# doorbell.net
KiCad netlist of a schematic drawn in EAGLE
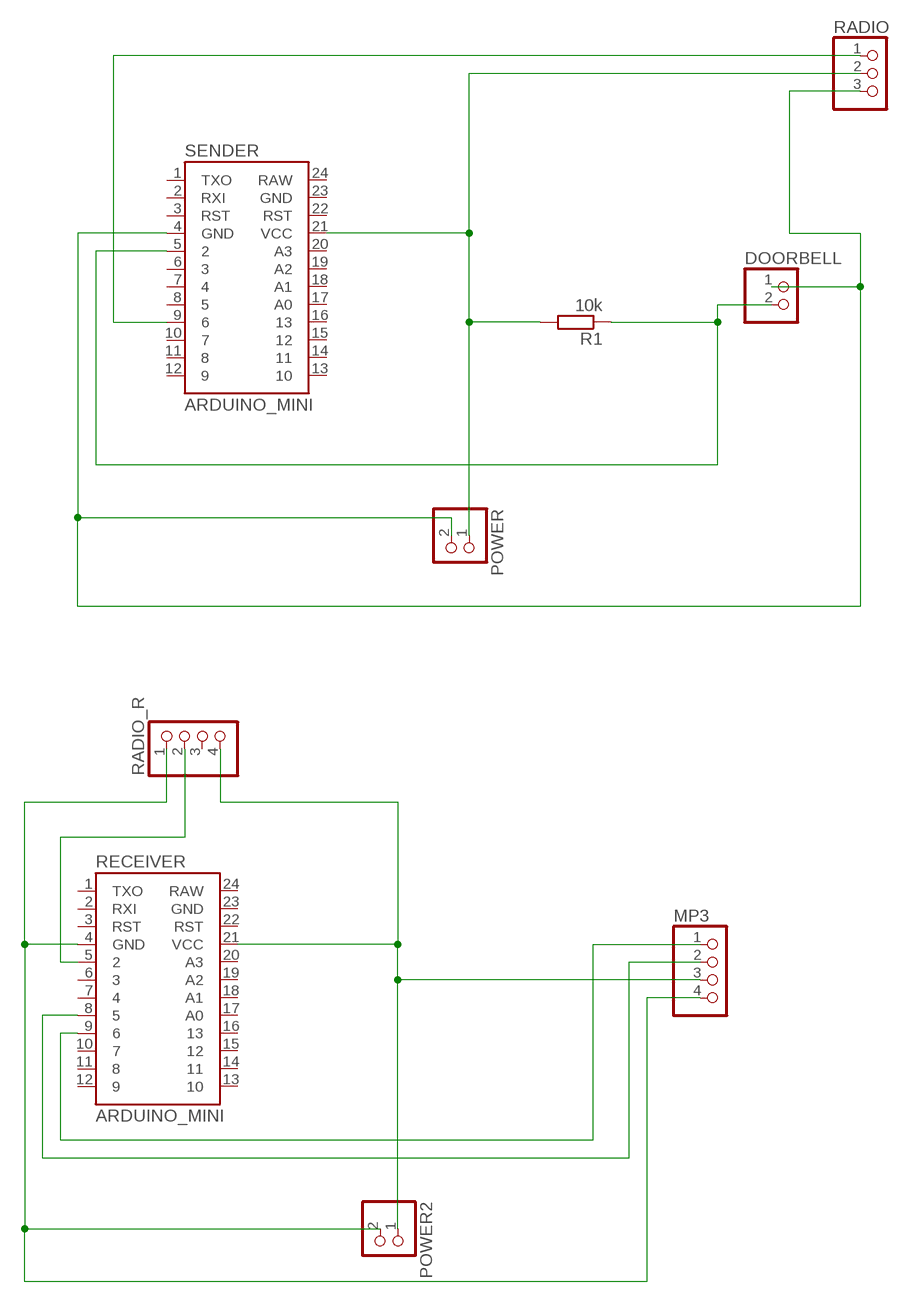
[diagram p0: schematic, sheet 1]

(export (version "E")
  (design (tool "Eeschema 10.0.6"))
  (components
    (comp (ref "DOORBELL")
      (value "PINHD-1X2/90")
      (footprint "eagle-import:1X02_90")
      (libsource (lib "eagle-import") (part "PINHD-1X2/90"))
    )
    (comp (ref "MP3")
      (value "PINHD-1X4/90")
      (footprint "eagle-import:1X04_90")
      (libsource (lib "eagle-import") (part "PINHD-1X4/90"))
    )
    (comp (ref "POWER")
      (value "PINHD-1X2/90")
      (footprint "eagle-import:1X02_90")
      (libsource (lib "eagle-import") (part "PINHD-1X2/90"))
    )
    (comp (ref "POWER2")
      (value "PINHD-1X2/90")
      (footprint "eagle-import:1X02_90")
      (libsource (lib "eagle-import") (part "PINHD-1X2/90"))
    )
    (comp (ref "R1")
      (value "10k")
      (footprint "eagle-import:0207_10")
      (libsource (lib "eagle-import") (part "R0207/10"))
    )
    (comp (ref "RADIO")
      (value "PINHD-1X3/90")
      (footprint "eagle-import:1X03_90")
      (libsource (lib "eagle-import") (part "PINHD-1X3/90"))
    )
    (comp (ref "RADIO_R")
      (value "PINHD-1X4/90")
      (footprint "eagle-import:1X04_90")
      (libsource (lib "eagle-import") (part "PINHD-1X4/90"))
    )
    (comp (ref "RECEIVER")
      (value "ARDUINO_MINI")
      (footprint "eagle-import:ARDUINO_MINI")
      (libsource (lib "eagle-import") (part "ARDUINO_MINI"))
    )
    (comp (ref "SENDER")
      (value "ARDUINO_MINI")
      (footprint "eagle-import:ARDUINO_MINI")
      (libsource (lib "eagle-import") (part "ARDUINO_MINI"))
    )
  )
  (nets
    (net (code "1") (name "Net-(DOORBELL-Pad1)") (class "Default")
      (node (ref "DOORBELL") (pin "1") (pinfunction "1_1") (pintype "passive"))
      (node (ref "POWER") (pin "2") (pinfunction "2_2") (pintype "passive"))
      (node (ref "RADIO") (pin "3") (pinfunction "3_3") (pintype "passive"))
      (node (ref "SENDER") (pin "4") (pinfunction "GND_4") (pintype "bidirectional"))
    )
    (net (code "2") (name "Net-(MP3-Pad4)") (class "Default")
      (node (ref "MP3") (pin "4") (pinfunction "4_4") (pintype "passive"))
      (node (ref "POWER2") (pin "2") (pinfunction "2_2") (pintype "passive"))
      (node (ref "RADIO_R") (pin "1") (pinfunction "1_1") (pintype "passive"))
      (node (ref "RECEIVER") (pin "4") (pinfunction "GND_4") (pintype "bidirectional"))
    )
    (net (code "3") (name "Net-(RECEIVER-2)") (class "Default")
      (node (ref "RADIO_R") (pin "2") (pinfunction "2_2") (pintype "passive"))
      (node (ref "RECEIVER") (pin "5") (pinfunction "2_5") (pintype "bidirectional"))
    )
    (net (code "4") (name "Net-(RECEIVER-5)") (class "Default")
      (node (ref "MP3") (pin "2") (pinfunction "2_2") (pintype "passive"))
      (node (ref "RECEIVER") (pin "8") (pinfunction "5_8") (pintype "bidirectional"))
    )
    (net (code "5") (name "Net-(RECEIVER-6)") (class "Default")
      (node (ref "MP3") (pin "1") (pinfunction "1_1") (pintype "passive"))
      (node (ref "RECEIVER") (pin "9") (pinfunction "6_9") (pintype "bidirectional"))
    )
    (net (code "6") (name "Net-(RECEIVER-VCC)") (class "Default")
      (node (ref "MP3") (pin "3") (pinfunction "3_3") (pintype "passive"))
      (node (ref "POWER2") (pin "1") (pinfunction "1_1") (pintype "passive"))
      (node (ref "RADIO_R") (pin "4") (pinfunction "4_4") (pintype "passive"))
      (node (ref "RECEIVER") (pin "21") (pinfunction "VCC_21") (pintype "bidirectional"))
    )
    (net (code "7") (name "Net-(SENDER-2)") (class "Default")
      (node (ref "DOORBELL") (pin "2") (pinfunction "2_2") (pintype "passive"))
      (node (ref "R1") (pin "1") (pinfunction "1_1") (pintype "passive"))
      (node (ref "SENDER") (pin "5") (pinfunction "2_5") (pintype "bidirectional"))
    )
    (net (code "8") (name "Net-(SENDER-6)") (class "Default")
      (node (ref "RADIO") (pin "1") (pinfunction "1_1") (pintype "passive"))
      (node (ref "SENDER") (pin "9") (pinfunction "6_9") (pintype "bidirectional"))
    )
    (net (code "9") (name "Net-(SENDER-VCC)") (class "Default")
      (node (ref "POWER") (pin "1") (pinfunction "1_1") (pintype "passive"))
      (node (ref "R1") (pin "2") (pinfunction "2_2") (pintype "passive"))
      (node (ref "RADIO") (pin "2") (pinfunction "2_2") (pintype "passive"))
      (node (ref "SENDER") (pin "21") (pinfunction "VCC_21") (pintype "bidirectional"))
    )
    (net (code "10") (name "unconnected-(RADIO_R-Pad3)") (class "Default")
      (node (ref "RADIO_R") (pin "3") (pinfunction "3_3") (pintype "passive"))
    )
    (net (code "11") (name "unconnected-(RECEIVER-3-Pad6)") (class "Default")
      (node (ref "RECEIVER") (pin "6") (pinfunction "3_6") (pintype "bidirectional"))
    )
    (net (code "12") (name "unconnected-(RECEIVER-4-Pad7)") (class "Default")
      (node (ref "RECEIVER") (pin "7") (pinfunction "4_7") (pintype "bidirectional"))
    )
    (net (code "13") (name "unconnected-(RECEIVER-7-Pad10)") (class "Default")
      (node (ref "RECEIVER") (pin "10") (pinfunction "7_10") (pintype "bidirectional"))
    )
    (net (code "14") (name "unconnected-(RECEIVER-8-Pad11)") (class "Default")
      (node (ref "RECEIVER") (pin "11") (pinfunction "8_11") (pintype "bidirectional"))
    )
    (net (code "15") (name "unconnected-(RECEIVER-9-Pad12)") (class "Default")
      (node (ref "RECEIVER") (pin "12") (pinfunction "9_12") (pintype "bidirectional"))
    )
    (net (code "16") (name "unconnected-(RECEIVER-10-Pad13)") (class "Default")
      (node (ref "RECEIVER") (pin "13") (pinfunction "10_13") (pintype "bidirectional"))
    )
    (net (code "17") (name "unconnected-(RECEIVER-11-Pad14)") (class "Default")
      (node (ref "RECEIVER") (pin "14") (pinfunction "11_14") (pintype "bidirectional"))
    )
    (net (code "18") (name "unconnected-(RECEIVER-12-Pad15)") (class "Default")
      (node (ref "RECEIVER") (pin "15") (pinfunction "12_15") (pintype "bidirectional"))
    )
    (net (code "19") (name "unconnected-(RECEIVER-13-Pad16)") (class "Default")
      (node (ref "RECEIVER") (pin "16") (pinfunction "13_16") (pintype "bidirectional"))
    )
    (net (code "20") (name "unconnected-(RECEIVER-A0-Pad17)") (class "Default")
      (node (ref "RECEIVER") (pin "17") (pinfunction "A0_17") (pintype "bidirectional"))
    )
    (net (code "21") (name "unconnected-(RECEIVER-A1-Pad18)") (class "Default")
      (node (ref "RECEIVER") (pin "18") (pinfunction "A1_18") (pintype "bidirectional"))
    )
    (net (code "22") (name "unconnected-(RECEIVER-A2-Pad19)") (class "Default")
      (node (ref "RECEIVER") (pin "19") (pinfunction "A2_19") (pintype "bidirectional"))
    )
    (net (code "23") (name "unconnected-(RECEIVER-A3-Pad20)") (class "Default")
      (node (ref "RECEIVER") (pin "20") (pinfunction "A3_20") (pintype "bidirectional"))
    )
    (net (code "24") (name "unconnected-(RECEIVER-GND-Pad23)") (class "Default")
      (node (ref "RECEIVER") (pin "23") (pinfunction "GND_23") (pintype "bidirectional"))
    )
    (net (code "25") (name "unconnected-(RECEIVER-RAW-Pad24)") (class "Default")
      (node (ref "RECEIVER") (pin "24") (pinfunction "RAW_24") (pintype "bidirectional"))
    )
    (net (code "26") (name "unconnected-(RECEIVER-RST-Pad3)") (class "Default")
      (node (ref "RECEIVER") (pin "3") (pinfunction "RST_3") (pintype "bidirectional"))
    )
    (net (code "27") (name "unconnected-(RECEIVER-RST-Pad22)") (class "Default")
      (node (ref "RECEIVER") (pin "22") (pinfunction "RST_22") (pintype "bidirectional"))
    )
    (net (code "28") (name "unconnected-(RECEIVER-RXI-Pad2)") (class "Default")
      (node (ref "RECEIVER") (pin "2") (pinfunction "RXI_2") (pintype "bidirectional"))
    )
    (net (code "29") (name "unconnected-(RECEIVER-TXO-Pad1)") (class "Default")
      (node (ref "RECEIVER") (pin "1") (pinfunction "TXO_1") (pintype "bidirectional"))
    )
    (net (code "30") (name "unconnected-(SENDER-3-Pad6)") (class "Default")
      (node (ref "SENDER") (pin "6") (pinfunction "3_6") (pintype "bidirectional"))
    )
    (net (code "31") (name "unconnected-(SENDER-4-Pad7)") (class "Default")
      (node (ref "SENDER") (pin "7") (pinfunction "4_7") (pintype "bidirectional"))
    )
    (net (code "32") (name "unconnected-(SENDER-5-Pad8)") (class "Default")
      (node (ref "SENDER") (pin "8") (pinfunction "5_8") (pintype "bidirectional"))
    )
    (net (code "33") (name "unconnected-(SENDER-7-Pad10)") (class "Default")
      (node (ref "SENDER") (pin "10") (pinfunction "7_10") (pintype "bidirectional"))
    )
    (net (code "34") (name "unconnected-(SENDER-8-Pad11)") (class "Default")
      (node (ref "SENDER") (pin "11") (pinfunction "8_11") (pintype "bidirectional"))
    )
    (net (code "35") (name "unconnected-(SENDER-9-Pad12)") (class "Default")
      (node (ref "SENDER") (pin "12") (pinfunction "9_12") (pintype "bidirectional"))
    )
    (net (code "36") (name "unconnected-(SENDER-10-Pad13)") (class "Default")
      (node (ref "SENDER") (pin "13") (pinfunction "10_13") (pintype "bidirectional"))
    )
    (net (code "37") (name "unconnected-(SENDER-11-Pad14)") (class "Default")
      (node (ref "SENDER") (pin "14") (pinfunction "11_14") (pintype "bidirectional"))
    )
    (net (code "38") (name "unconnected-(SENDER-12-Pad15)") (class "Default")
      (node (ref "SENDER") (pin "15") (pinfunction "12_15") (pintype "bidirectional"))
    )
    (net (code "39") (name "unconnected-(SENDER-13-Pad16)") (class "Default")
      (node (ref "SENDER") (pin "16") (pinfunction "13_16") (pintype "bidirectional"))
    )
    (net (code "40") (name "unconnected-(SENDER-A0-Pad17)") (class "Default")
      (node (ref "SENDER") (pin "17") (pinfunction "A0_17") (pintype "bidirectional"))
    )
    (net (code "41") (name "unconnected-(SENDER-A1-Pad18)") (class "Default")
      (node (ref "SENDER") (pin "18") (pinfunction "A1_18") (pintype "bidirectional"))
    )
    (net (code "42") (name "unconnected-(SENDER-A2-Pad19)") (class "Default")
      (node (ref "SENDER") (pin "19") (pinfunction "A2_19") (pintype "bidirectional"))
    )
    (net (code "43") (name "unconnected-(SENDER-A3-Pad20)") (class "Default")
      (node (ref "SENDER") (pin "20") (pinfunction "A3_20") (pintype "bidirectional"))
    )
    (net (code "44") (name "unconnected-(SENDER-GND-Pad23)") (class "Default")
      (node (ref "SENDER") (pin "23") (pinfunction "GND_23") (pintype "bidirectional"))
    )
    (net (code "45") (name "unconnected-(SENDER-RAW-Pad24)") (class "Default")
      (node (ref "SENDER") (pin "24") (pinfunction "RAW_24") (pintype "bidirectional"))
    )
    (net (code "46") (name "unconnected-(SENDER-RST-Pad3)") (class "Default")
      (node (ref "SENDER") (pin "3") (pinfunction "RST_3") (pintype "bidirectional"))
    )
    (net (code "47") (name "unconnected-(SENDER-RST-Pad22)") (class "Default")
      (node (ref "SENDER") (pin "22") (pinfunction "RST_22") (pintype "bidirectional"))
    )
    (net (code "48") (name "unconnected-(SENDER-RXI-Pad2)") (class "Default")
      (node (ref "SENDER") (pin "2") (pinfunction "RXI_2") (pintype "bidirectional"))
    )
    (net (code "49") (name "unconnected-(SENDER-TXO-Pad1)") (class "Default")
      (node (ref "SENDER") (pin "1") (pinfunction "TXO_1") (pintype "bidirectional"))
    )
  )
)
